# IQ.net
KiCad netlist of a schematic drawn in Altium Designer
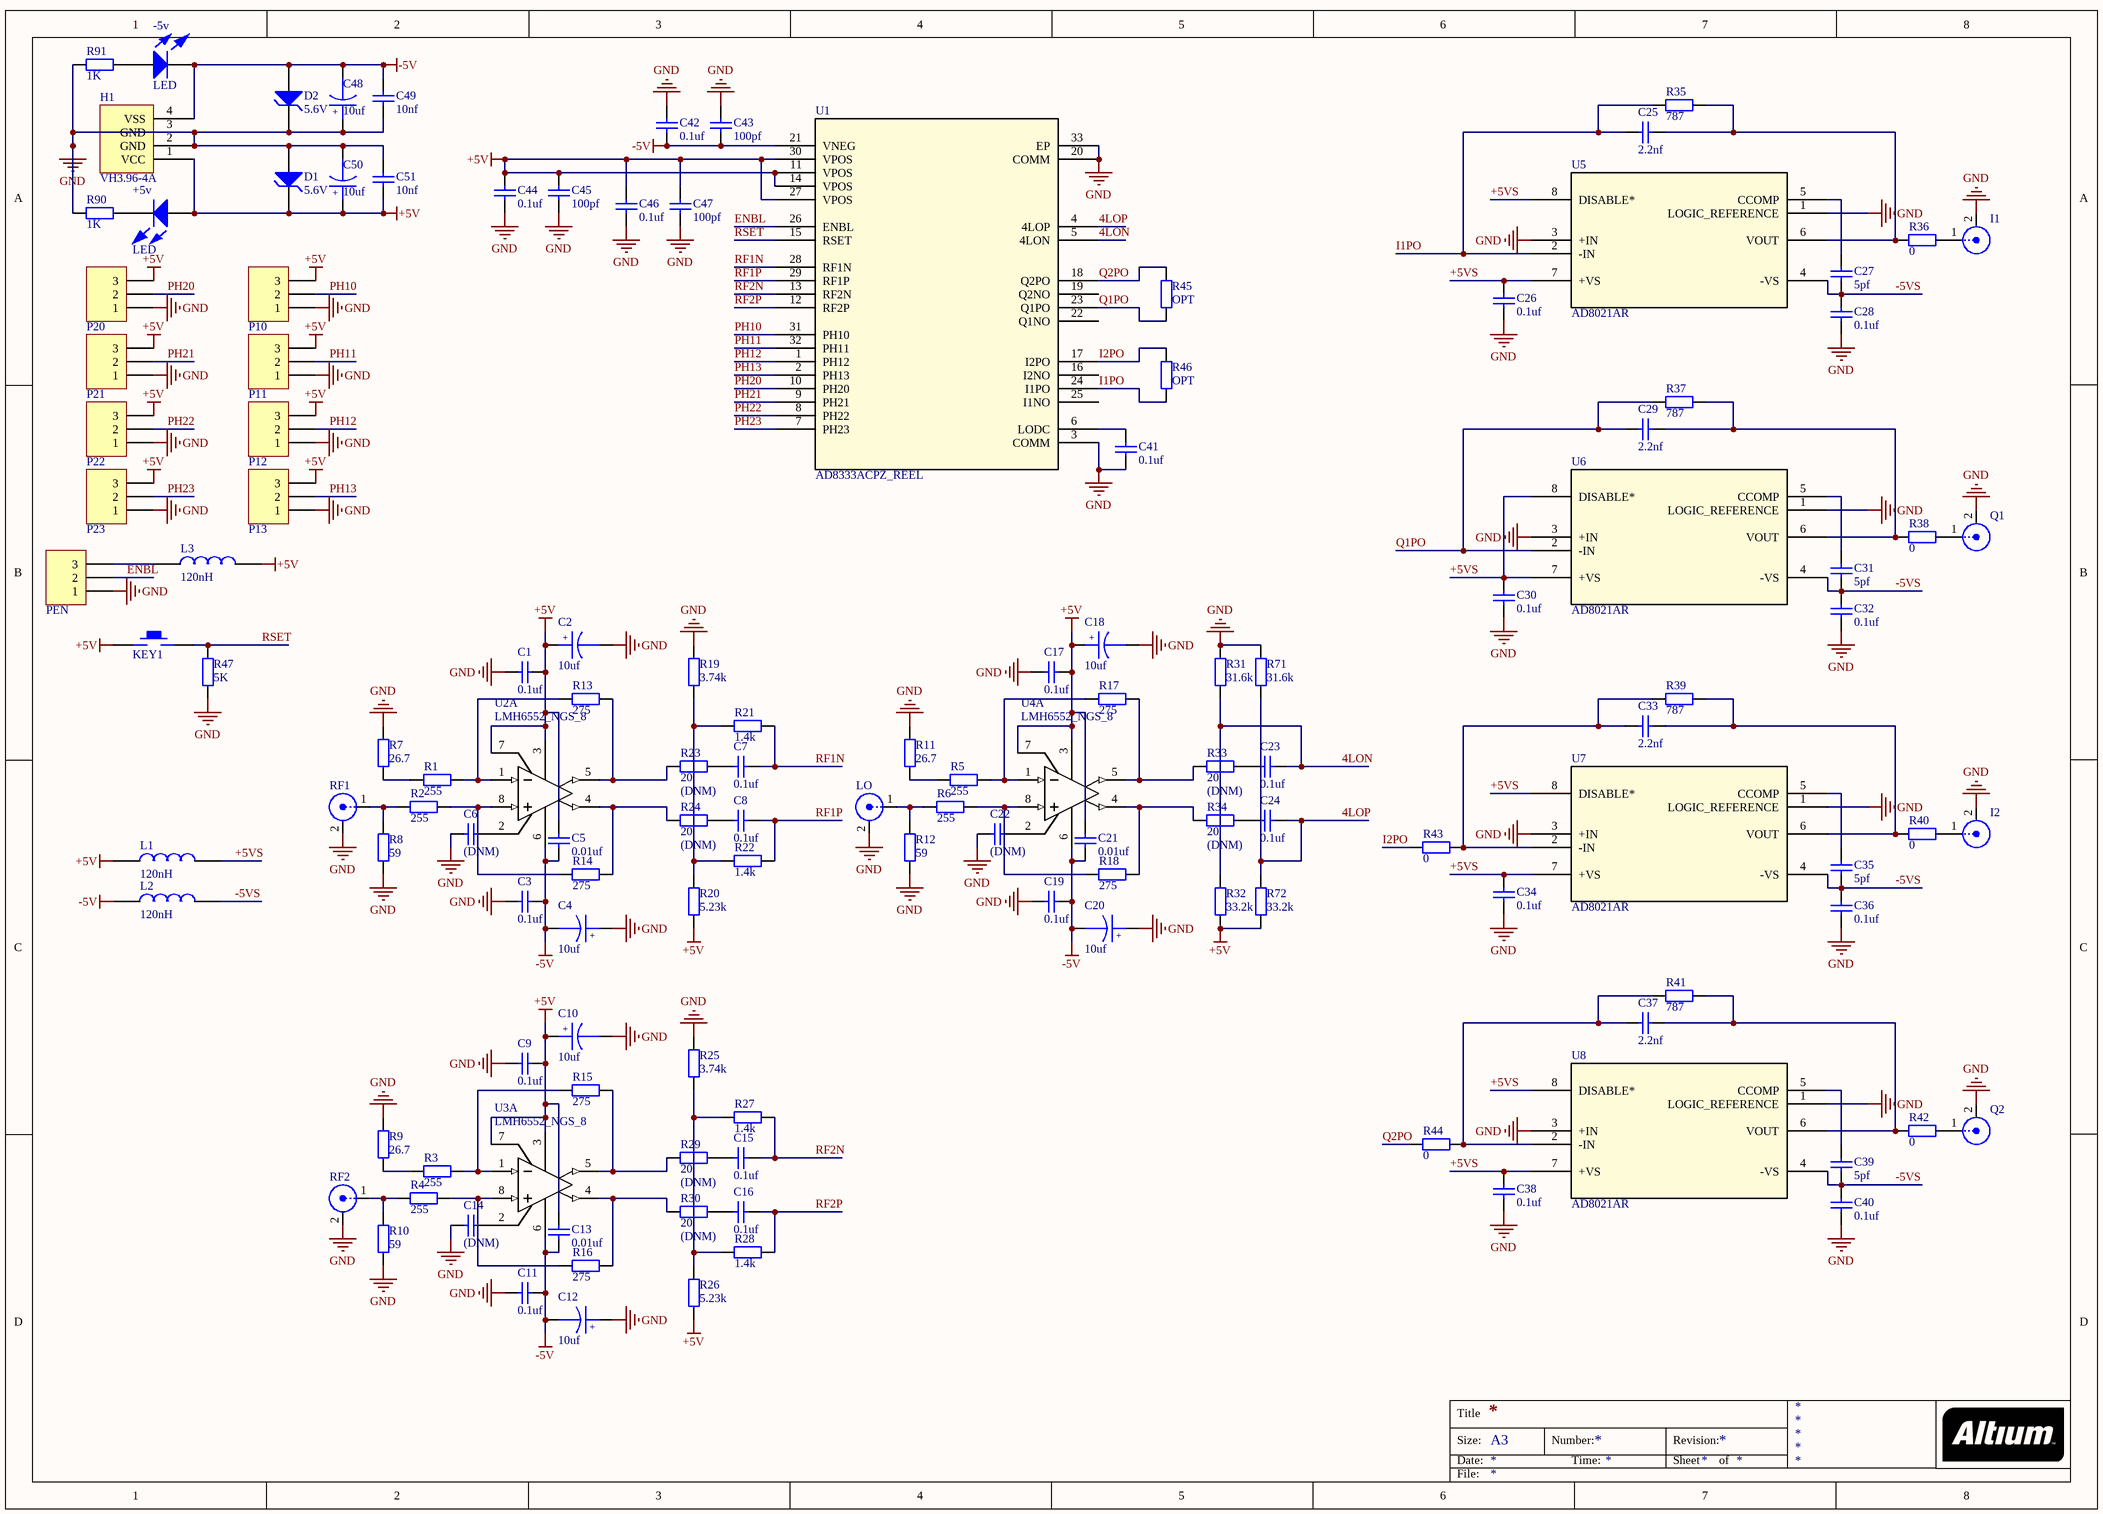
[diagram p0: IQ解调器原理图.SchDoc]

(export (version "E")
  (design (tool "Eeschema 10.0.6"))
  (components
    (comp (ref "+5v") (value "LED") (footprint "0805") (libsource (lib "IQ解调器-原理图") (part "LED")))
    (comp (ref "-5v") (value "LED") (footprint "0805") (libsource (lib "IQ解调器-原理图") (part "LED")))
    (comp (ref "C1")
      (value "0.1uf")
      (footprint "0603C")
      (description "无极性电容")
      (fields (field (name "Comment") "Cap"))
      (libsource (lib "IQ解调器-原理图") (part "Cap"))
    )
    (comp (ref "C2")
      (value "10uf")
      (footprint "3216C-TYPE_A")
      (libsource (lib "IQ解调器-原理图") (part "钽电容Type-A"))
    )
    (comp (ref "C3")
      (value "0.1uf")
      (footprint "0603C")
      (description "无极性电容")
      (fields (field (name "Comment") "Cap"))
      (libsource (lib "IQ解调器-原理图") (part "Cap"))
    )
    (comp (ref "C4")
      (value "10uf")
      (footprint "3216C-TYPE_A")
      (libsource (lib "IQ解调器-原理图") (part "钽电容Type-A"))
    )
    (comp (ref "C5")
      (value "0.01uf")
      (footprint "0603C")
      (description "无极性电容")
      (fields (field (name "Comment") "Cap"))
      (libsource (lib "IQ解调器-原理图") (part "Cap"))
    )
    (comp (ref "C6")
      (value "(DNM)")
      (footprint "0603C")
      (description "无极性电容")
      (fields (field (name "Comment") "Cap"))
      (libsource (lib "IQ解调器-原理图") (part "Cap"))
    )
    (comp (ref "C7")
      (value "0.1uf")
      (footprint "0603C")
      (description "无极性电容")
      (fields (field (name "Comment") "Cap"))
      (libsource (lib "IQ解调器-原理图") (part "Cap"))
    )
    (comp (ref "C8")
      (value "0.1uf")
      (footprint "0603C")
      (description "无极性电容")
      (fields (field (name "Comment") "Cap"))
      (libsource (lib "IQ解调器-原理图") (part "Cap"))
    )
    (comp (ref "C9")
      (value "0.1uf")
      (footprint "0603C")
      (description "无极性电容")
      (fields (field (name "Comment") "Cap"))
      (libsource (lib "IQ解调器-原理图") (part "Cap"))
    )
    (comp (ref "C10")
      (value "10uf")
      (footprint "3216C-TYPE_A")
      (libsource (lib "IQ解调器-原理图") (part "钽电容Type-A"))
    )
    (comp (ref "C11")
      (value "0.1uf")
      (footprint "0603C")
      (description "无极性电容")
      (fields (field (name "Comment") "Cap"))
      (libsource (lib "IQ解调器-原理图") (part "Cap"))
    )
    (comp (ref "C12")
      (value "10uf")
      (footprint "3216C-TYPE_A")
      (libsource (lib "IQ解调器-原理图") (part "钽电容Type-A"))
    )
    (comp (ref "C13")
      (value "0.01uf")
      (footprint "0603C")
      (description "无极性电容")
      (fields (field (name "Comment") "Cap"))
      (libsource (lib "IQ解调器-原理图") (part "Cap"))
    )
    (comp (ref "C14")
      (value "(DNM)")
      (footprint "0603C")
      (description "无极性电容")
      (fields (field (name "Comment") "Cap"))
      (libsource (lib "IQ解调器-原理图") (part "Cap"))
    )
    (comp (ref "C15")
      (value "0.1uf")
      (footprint "0603C")
      (description "无极性电容")
      (fields (field (name "Comment") "Cap"))
      (libsource (lib "IQ解调器-原理图") (part "Cap"))
    )
    (comp (ref "C16")
      (value "0.1uf")
      (footprint "0603C")
      (description "无极性电容")
      (fields (field (name "Comment") "Cap"))
      (libsource (lib "IQ解调器-原理图") (part "Cap"))
    )
    (comp (ref "C17")
      (value "0.1uf")
      (footprint "0603C")
      (description "无极性电容")
      (fields (field (name "Comment") "Cap"))
      (libsource (lib "IQ解调器-原理图") (part "Cap"))
    )
    (comp (ref "C18")
      (value "10uf")
      (footprint "3216C-TYPE_A")
      (libsource (lib "IQ解调器-原理图") (part "钽电容Type-A"))
    )
    (comp (ref "C19")
      (value "0.1uf")
      (footprint "0603C")
      (description "无极性电容")
      (fields (field (name "Comment") "Cap"))
      (libsource (lib "IQ解调器-原理图") (part "Cap"))
    )
    (comp (ref "C20")
      (value "10uf")
      (footprint "3216C-TYPE_A")
      (libsource (lib "IQ解调器-原理图") (part "钽电容Type-A"))
    )
    (comp (ref "C21")
      (value "0.01uf")
      (footprint "0603C")
      (description "无极性电容")
      (fields (field (name "Comment") "Cap"))
      (libsource (lib "IQ解调器-原理图") (part "Cap"))
    )
    (comp (ref "C22")
      (value "(DNM)")
      (footprint "0603C")
      (description "无极性电容")
      (fields (field (name "Comment") "Cap"))
      (libsource (lib "IQ解调器-原理图") (part "Cap"))
    )
    (comp (ref "C23")
      (value "0.1uf")
      (footprint "0603C")
      (description "无极性电容")
      (fields (field (name "Comment") "Cap"))
      (libsource (lib "IQ解调器-原理图") (part "Cap"))
    )
    (comp (ref "C24")
      (value "0.1uf")
      (footprint "0603C")
      (description "无极性电容")
      (fields (field (name "Comment") "Cap"))
      (libsource (lib "IQ解调器-原理图") (part "Cap"))
    )
    (comp (ref "C25")
      (value "2.2nf")
      (footprint "0603C")
      (description "无极性电容")
      (fields (field (name "Comment") "Cap"))
      (libsource (lib "IQ解调器-原理图") (part "Cap"))
    )
    (comp (ref "C26")
      (value "0.1uf")
      (footprint "0603C")
      (description "无极性电容")
      (fields (field (name "Comment") "Cap"))
      (libsource (lib "IQ解调器-原理图") (part "Cap"))
    )
    (comp (ref "C27")
      (value "5pf")
      (footprint "0603C")
      (description "无极性电容")
      (fields (field (name "Comment") "Cap"))
      (libsource (lib "IQ解调器-原理图") (part "Cap"))
    )
    (comp (ref "C28")
      (value "0.1uf")
      (footprint "0603C")
      (description "无极性电容")
      (fields (field (name "Comment") "Cap"))
      (libsource (lib "IQ解调器-原理图") (part "Cap"))
    )
    (comp (ref "C29")
      (value "2.2nf")
      (footprint "0603C")
      (description "无极性电容")
      (fields (field (name "Comment") "Cap"))
      (libsource (lib "IQ解调器-原理图") (part "Cap"))
    )
    (comp (ref "C30")
      (value "0.1uf")
      (footprint "0603C")
      (description "无极性电容")
      (fields (field (name "Comment") "Cap"))
      (libsource (lib "IQ解调器-原理图") (part "Cap"))
    )
    (comp (ref "C31")
      (value "5pf")
      (footprint "0603C")
      (description "无极性电容")
      (fields (field (name "Comment") "Cap"))
      (libsource (lib "IQ解调器-原理图") (part "Cap"))
    )
    (comp (ref "C32")
      (value "0.1uf")
      (footprint "0603C")
      (description "无极性电容")
      (fields (field (name "Comment") "Cap"))
      (libsource (lib "IQ解调器-原理图") (part "Cap"))
    )
    (comp (ref "C33")
      (value "2.2nf")
      (footprint "0603C")
      (description "无极性电容")
      (fields (field (name "Comment") "Cap"))
      (libsource (lib "IQ解调器-原理图") (part "Cap"))
    )
    (comp (ref "C34")
      (value "0.1uf")
      (footprint "0603C")
      (description "无极性电容")
      (fields (field (name "Comment") "Cap"))
      (libsource (lib "IQ解调器-原理图") (part "Cap"))
    )
    (comp (ref "C35")
      (value "5pf")
      (footprint "0603C")
      (description "无极性电容")
      (fields (field (name "Comment") "Cap"))
      (libsource (lib "IQ解调器-原理图") (part "Cap"))
    )
    (comp (ref "C36")
      (value "0.1uf")
      (footprint "0603C")
      (description "无极性电容")
      (fields (field (name "Comment") "Cap"))
      (libsource (lib "IQ解调器-原理图") (part "Cap"))
    )
    (comp (ref "C37")
      (value "2.2nf")
      (footprint "0603C")
      (description "无极性电容")
      (fields (field (name "Comment") "Cap"))
      (libsource (lib "IQ解调器-原理图") (part "Cap"))
    )
    (comp (ref "C38")
      (value "0.1uf")
      (footprint "0603C")
      (description "无极性电容")
      (fields (field (name "Comment") "Cap"))
      (libsource (lib "IQ解调器-原理图") (part "Cap"))
    )
    (comp (ref "C39")
      (value "5pf")
      (footprint "0603C")
      (description "无极性电容")
      (fields (field (name "Comment") "Cap"))
      (libsource (lib "IQ解调器-原理图") (part "Cap"))
    )
    (comp (ref "C40")
      (value "0.1uf")
      (footprint "0603C")
      (description "无极性电容")
      (fields (field (name "Comment") "Cap"))
      (libsource (lib "IQ解调器-原理图") (part "Cap"))
    )
    (comp (ref "C41")
      (value "0.1uf")
      (footprint "0603C")
      (description "无极性电容")
      (fields (field (name "Comment") "Cap"))
      (libsource (lib "IQ解调器-原理图") (part "Cap"))
    )
    (comp (ref "C42")
      (value "0.1uf")
      (footprint "0603C")
      (description "无极性电容")
      (fields (field (name "Comment") "Cap"))
      (libsource (lib "IQ解调器-原理图") (part "Cap"))
    )
    (comp (ref "C43")
      (value "100pf")
      (footprint "0603C")
      (description "无极性电容")
      (fields (field (name "Comment") "Cap"))
      (libsource (lib "IQ解调器-原理图") (part "Cap"))
    )
    (comp (ref "C44")
      (value "0.1uf")
      (footprint "0603C")
      (description "无极性电容")
      (fields (field (name "Comment") "Cap"))
      (libsource (lib "IQ解调器-原理图") (part "Cap"))
    )
    (comp (ref "C45")
      (value "100pf")
      (footprint "0603C")
      (description "无极性电容")
      (fields (field (name "Comment") "Cap"))
      (libsource (lib "IQ解调器-原理图") (part "Cap"))
    )
    (comp (ref "C46")
      (value "0.1uf")
      (footprint "0603C")
      (description "无极性电容")
      (fields (field (name "Comment") "Cap"))
      (libsource (lib "IQ解调器-原理图") (part "Cap"))
    )
    (comp (ref "C47")
      (value "100pf")
      (footprint "0603C")
      (description "无极性电容")
      (fields (field (name "Comment") "Cap"))
      (libsource (lib "IQ解调器-原理图") (part "Cap"))
    )
    (comp (ref "C48")
      (value "10uf")
      (footprint "3216C-TYPE_A")
      (libsource (lib "IQ解调器-原理图") (part "钽电容Type-A"))
    )
    (comp (ref "C49")
      (value "10nf")
      (footprint "0603C")
      (description "无极性电容")
      (fields (field (name "Comment") "Cap"))
      (libsource (lib "IQ解调器-原理图") (part "Cap"))
    )
    (comp (ref "C50")
      (value "10uf")
      (footprint "3216C-TYPE_A")
      (libsource (lib "IQ解调器-原理图") (part "钽电容Type-A"))
    )
    (comp (ref "C51")
      (value "10nf")
      (footprint "0603C")
      (description "无极性电容")
      (fields (field (name "Comment") "Cap"))
      (libsource (lib "IQ解调器-原理图") (part "Cap"))
    )
    (comp (ref "D1")
      (value "5.6V")
      (footprint "SMA/DO-214AC")
      (libsource (lib "IQ解调器-原理图") (part "肖特基-5.6V"))
    )
    (comp (ref "D2")
      (value "5.6V")
      (footprint "SMA/DO-214AC")
      (libsource (lib "IQ解调器-原理图") (part "肖特基-5.6V"))
    )
    (comp (ref "H1")
      (value "VH3.96-4A")
      (footprint "VH3.96-4P")
      (libsource (lib "IQ解调器-原理图") (part "VH3.96-4A"))
    )
    (comp (ref "I1") (value "SMA") (footprint "SMA-2") (libsource (lib "IQ解调器-原理图") (part "SMA-2")))
    (comp (ref "I2") (value "SMA") (footprint "SMA-2") (libsource (lib "IQ解调器-原理图") (part "SMA-2")))
    (comp (ref "KEY1")
      (value "KEY_M")
      (footprint "KEY_M")
      (libsource (lib "MiniSTM32 V3.0封装库") (part "KEY_M"))
    )
    (comp (ref "L1")
      (value "120nH")
      (footprint "0603R")
      (description "0603电感")
      (libsource (lib "IQ解调器-原理图") (part "0603电感"))
    )
    (comp (ref "L2")
      (value "120nH")
      (footprint "0603R")
      (description "0603电感")
      (libsource (lib "IQ解调器-原理图") (part "0603电感"))
    )
    (comp (ref "L3")
      (value "120nH")
      (footprint "0603R")
      (description "0603电感")
      (libsource (lib "IQ解调器-原理图") (part "0603电感"))
    )
    (comp (ref "LO") (value "SMA") (footprint "SMA-2") (libsource (lib "IQ解调器-原理图") (part "SMA-2")))
    (comp (ref "P10")
      (value "Header 3")
      (footprint "HDR3X1_A")
      (description "接插件")
      (libsource (lib "Fszhang") (part "Header 3"))
    )
    (comp (ref "P11")
      (value "Header 3")
      (footprint "HDR3X1_A")
      (description "接插件")
      (libsource (lib "Fszhang") (part "Header 3"))
    )
    (comp (ref "P12")
      (value "Header 3")
      (footprint "HDR3X1_A")
      (description "接插件")
      (libsource (lib "Fszhang") (part "Header 3"))
    )
    (comp (ref "P13")
      (value "Header 3")
      (footprint "HDR3X1_A")
      (description "接插件")
      (libsource (lib "Fszhang") (part "Header 3"))
    )
    (comp (ref "P20")
      (value "Header 3")
      (footprint "HDR3X1_A")
      (description "接插件")
      (libsource (lib "Fszhang") (part "Header 3"))
    )
    (comp (ref "P21")
      (value "Header 3")
      (footprint "HDR3X1_A")
      (description "接插件")
      (libsource (lib "Fszhang") (part "Header 3"))
    )
    (comp (ref "P22")
      (value "Header 3")
      (footprint "HDR3X1_A")
      (description "接插件")
      (libsource (lib "Fszhang") (part "Header 3"))
    )
    (comp (ref "P23")
      (value "Header 3")
      (footprint "HDR3X1_A")
      (description "接插件")
      (libsource (lib "Fszhang") (part "Header 3"))
    )
    (comp (ref "PEN")
      (value "Header 3")
      (footprint "HDR3X1_A")
      (description "接插件")
      (libsource (lib "Fszhang") (part "Header 3"))
    )
    (comp (ref "Q1") (value "SMA") (footprint "SMA-2") (libsource (lib "IQ解调器-原理图") (part "SMA-2")))
    (comp (ref "Q2") (value "SMA") (footprint "SMA-2") (libsource (lib "IQ解调器-原理图") (part "SMA-2")))
    (comp (ref "R1")
      (value "255")
      (footprint "0603R")
      (description "贴片电阻")
      (fields (field (name "Comment") "Res1"))
      (libsource (lib "IQ解调器-原理图") (part "Res1"))
    )
    (comp (ref "R2")
      (value "255")
      (footprint "0603R")
      (description "贴片电阻")
      (fields (field (name "Comment") "Res1"))
      (libsource (lib "IQ解调器-原理图") (part "Res1"))
    )
    (comp (ref "R3")
      (value "255")
      (footprint "0603R")
      (description "贴片电阻")
      (fields (field (name "Comment") "Res1"))
      (libsource (lib "IQ解调器-原理图") (part "Res1"))
    )
    (comp (ref "R4")
      (value "255")
      (footprint "0603R")
      (description "贴片电阻")
      (fields (field (name "Comment") "Res1"))
      (libsource (lib "IQ解调器-原理图") (part "Res1"))
    )
    (comp (ref "R5")
      (value "255")
      (footprint "0603R")
      (description "贴片电阻")
      (fields (field (name "Comment") "Res1"))
      (libsource (lib "IQ解调器-原理图") (part "Res1"))
    )
    (comp (ref "R6")
      (value "255")
      (footprint "0603R")
      (description "贴片电阻")
      (fields (field (name "Comment") "Res1"))
      (libsource (lib "IQ解调器-原理图") (part "Res1"))
    )
    (comp (ref "R7")
      (value "26.7")
      (footprint "0603R")
      (description "贴片电阻")
      (fields (field (name "Comment") "Res1"))
      (libsource (lib "") (part "Res1_1"))
    )
    (comp (ref "R8")
      (value "59")
      (footprint "0603R")
      (description "贴片电阻")
      (fields (field (name "Comment") "Res1"))
      (libsource (lib "") (part "Res1_1"))
    )
    (comp (ref "R9")
      (value "26.7")
      (footprint "0603R")
      (description "贴片电阻")
      (fields (field (name "Comment") "Res1"))
      (libsource (lib "") (part "Res1_1"))
    )
    (comp (ref "R10")
      (value "59")
      (footprint "0603R")
      (description "贴片电阻")
      (fields (field (name "Comment") "Res1"))
      (libsource (lib "") (part "Res1_1"))
    )
    (comp (ref "R11")
      (value "26.7")
      (footprint "0603R")
      (description "贴片电阻")
      (fields (field (name "Comment") "Res1"))
      (libsource (lib "") (part "Res1_1"))
    )
    (comp (ref "R12")
      (value "59")
      (footprint "0603R")
      (description "贴片电阻")
      (fields (field (name "Comment") "Res1"))
      (libsource (lib "") (part "Res1_1"))
    )
    (comp (ref "R13")
      (value "275")
      (footprint "0603R")
      (description "贴片电阻")
      (fields (field (name "Comment") "Res1"))
      (libsource (lib "IQ解调器-原理图") (part "Res1"))
    )
    (comp (ref "R14")
      (value "275")
      (footprint "0603R")
      (description "贴片电阻")
      (fields (field (name "Comment") "Res1"))
      (libsource (lib "IQ解调器-原理图") (part "Res1"))
    )
    (comp (ref "R15")
      (value "275")
      (footprint "0603R")
      (description "贴片电阻")
      (fields (field (name "Comment") "Res1"))
      (libsource (lib "IQ解调器-原理图") (part "Res1"))
    )
    (comp (ref "R16")
      (value "275")
      (footprint "0603R")
      (description "贴片电阻")
      (fields (field (name "Comment") "Res1"))
      (libsource (lib "IQ解调器-原理图") (part "Res1"))
    )
    (comp (ref "R17")
      (value "275")
      (footprint "0603R")
      (description "贴片电阻")
      (fields (field (name "Comment") "Res1"))
      (libsource (lib "IQ解调器-原理图") (part "Res1"))
    )
    (comp (ref "R18")
      (value "275")
      (footprint "0603R")
      (description "贴片电阻")
      (fields (field (name "Comment") "Res1"))
      (libsource (lib "IQ解调器-原理图") (part "Res1"))
    )
    (comp (ref "R19")
      (value "3.74k")
      (footprint "0603R")
      (description "贴片电阻")
      (fields (field (name "Comment") "Res1"))
      (libsource (lib "") (part "Res1_1"))
    )
    (comp (ref "R20")
      (value "5.23k")
      (footprint "0603R")
      (description "贴片电阻")
      (fields (field (name "Comment") "Res1"))
      (libsource (lib "") (part "Res1_1"))
    )
    (comp (ref "R21")
      (value "1.4k")
      (footprint "0603R")
      (description "贴片电阻")
      (fields (field (name "Comment") "Res1"))
      (libsource (lib "") (part "Res1_2"))
    )
    (comp (ref "R22")
      (value "1.4k")
      (footprint "0603R")
      (description "贴片电阻")
      (fields (field (name "Comment") "Res1"))
      (libsource (lib "IQ解调器-原理图") (part "Res1"))
    )
    (comp (ref "R23")
      (value "(DNM)")
      (footprint "0603R")
      (description "贴片电阻")
      (fields (field (name "ALTIUM_VALUE") "20"))
      (libsource (lib "IQ解调器-原理图") (part "Res1"))
    )
    (comp (ref "R24")
      (value "(DNM)")
      (footprint "0603R")
      (description "贴片电阻")
      (fields (field (name "ALTIUM_VALUE") "20"))
      (libsource (lib "IQ解调器-原理图") (part "Res1"))
    )
    (comp (ref "R25")
      (value "3.74k")
      (footprint "0603R")
      (description "贴片电阻")
      (fields (field (name "Comment") "Res1"))
      (libsource (lib "") (part "Res1_1"))
    )
    (comp (ref "R26")
      (value "5.23k")
      (footprint "0603R")
      (description "贴片电阻")
      (fields (field (name "Comment") "Res1"))
      (libsource (lib "") (part "Res1_1"))
    )
    (comp (ref "R27")
      (value "1.4k")
      (footprint "0603R")
      (description "贴片电阻")
      (fields (field (name "Comment") "Res1"))
      (libsource (lib "") (part "Res1_2"))
    )
    (comp (ref "R28")
      (value "1.4k")
      (footprint "0603R")
      (description "贴片电阻")
      (fields (field (name "Comment") "Res1"))
      (libsource (lib "IQ解调器-原理图") (part "Res1"))
    )
    (comp (ref "R29")
      (value "(DNM)")
      (footprint "0603R")
      (description "贴片电阻")
      (fields (field (name "ALTIUM_VALUE") "20"))
      (libsource (lib "IQ解调器-原理图") (part "Res1"))
    )
    (comp (ref "R30")
      (value "(DNM)")
      (footprint "0603R")
      (description "贴片电阻")
      (fields (field (name "ALTIUM_VALUE") "20"))
      (libsource (lib "IQ解调器-原理图") (part "Res1"))
    )
    (comp (ref "R31")
      (value "31.6k")
      (footprint "0603R")
      (description "贴片电阻")
      (fields (field (name "Comment") "Res1"))
      (libsource (lib "") (part "Res1_1"))
    )
    (comp (ref "R32")
      (value "33.2k")
      (footprint "0603R")
      (description "贴片电阻")
      (fields (field (name "Comment") "Res1"))
      (libsource (lib "") (part "Res1_1"))
    )
    (comp (ref "R33")
      (value "(DNM)")
      (footprint "0603R")
      (description "贴片电阻")
      (fields (field (name "ALTIUM_VALUE") "20"))
      (libsource (lib "IQ解调器-原理图") (part "Res1"))
    )
    (comp (ref "R34")
      (value "(DNM)")
      (footprint "0603R")
      (description "贴片电阻")
      (fields (field (name "ALTIUM_VALUE") "20"))
      (libsource (lib "IQ解调器-原理图") (part "Res1"))
    )
    (comp (ref "R35")
      (value "787")
      (footprint "0603R")
      (description "贴片电阻")
      (fields (field (name "Comment") "Res1"))
      (libsource (lib "IQ解调器-原理图") (part "Res1"))
    )
    (comp (ref "R36")
      (value "0")
      (footprint "0603R")
      (description "贴片电阻")
      (fields (field (name "Comment") "Res1"))
      (libsource (lib "IQ解调器-原理图") (part "Res1"))
    )
    (comp (ref "R37")
      (value "787")
      (footprint "0603R")
      (description "贴片电阻")
      (fields (field (name "Comment") "Res1"))
      (libsource (lib "IQ解调器-原理图") (part "Res1"))
    )
    (comp (ref "R38")
      (value "0")
      (footprint "0603R")
      (description "贴片电阻")
      (fields (field (name "Comment") "Res1"))
      (libsource (lib "IQ解调器-原理图") (part "Res1"))
    )
    (comp (ref "R39")
      (value "787")
      (footprint "0603R")
      (description "贴片电阻")
      (fields (field (name "Comment") "Res1"))
      (libsource (lib "IQ解调器-原理图") (part "Res1"))
    )
    (comp (ref "R40")
      (value "0")
      (footprint "0603R")
      (description "贴片电阻")
      (fields (field (name "Comment") "Res1"))
      (libsource (lib "IQ解调器-原理图") (part "Res1"))
    )
    (comp (ref "R41")
      (value "787")
      (footprint "0603R")
      (description "贴片电阻")
      (fields (field (name "Comment") "Res1"))
      (libsource (lib "IQ解调器-原理图") (part "Res1"))
    )
    (comp (ref "R42")
      (value "0")
      (footprint "0603R")
      (description "贴片电阻")
      (fields (field (name "Comment") "Res1"))
      (libsource (lib "IQ解调器-原理图") (part "Res1"))
    )
    (comp (ref "R43")
      (value "0")
      (footprint "0603R")
      (description "贴片电阻")
      (fields (field (name "Comment") "Res1"))
      (libsource (lib "IQ解调器-原理图") (part "Res1"))
    )
    (comp (ref "R44")
      (value "0")
      (footprint "0603R")
      (description "贴片电阻")
      (fields (field (name "Comment") "Res1"))
      (libsource (lib "IQ解调器-原理图") (part "Res1"))
    )
    (comp (ref "R45")
      (value "OPT")
      (footprint "0603R")
      (description "贴片电阻")
      (fields (field (name "Comment") "Res1"))
      (libsource (lib "") (part "Res1_1"))
    )
    (comp (ref "R46")
      (value "OPT")
      (footprint "0603R")
      (description "贴片电阻")
      (fields (field (name "Comment") "Res1"))
      (libsource (lib "") (part "Res1_1"))
    )
    (comp (ref "R47")
      (value "5K")
      (footprint "0603R")
      (description "贴片电阻")
      (fields (field (name "Comment") "Res1"))
      (libsource (lib "") (part "Res1_1"))
    )
    (comp (ref "R71")
      (value "31.6k")
      (footprint "0603R")
      (description "贴片电阻")
      (fields (field (name "Comment") "Res1"))
      (libsource (lib "") (part "Res1_1"))
    )
    (comp (ref "R72")
      (value "33.2k")
      (footprint "0603R")
      (description "贴片电阻")
      (fields (field (name "Comment") "Res1"))
      (libsource (lib "") (part "Res1_1"))
    )
    (comp (ref "R90")
      (value "1K")
      (footprint "0603R")
      (description "贴片电阻")
      (fields (field (name "Comment") "Res1"))
      (libsource (lib "IQ解调器-原理图") (part "Res1"))
    )
    (comp (ref "R91")
      (value "1K")
      (footprint "0603R")
      (description "贴片电阻")
      (fields (field (name "Comment") "Res1"))
      (libsource (lib "IQ解调器-原理图") (part "Res1"))
    )
    (comp (ref "RF1") (value "SMA") (footprint "SMA-2") (libsource (lib "IQ解调器-原理图") (part "SMA-2")))
    (comp (ref "RF2") (value "SMA") (footprint "SMA-2") (libsource (lib "IQ解调器-原理图") (part "SMA-2")))
    (comp (ref "U1")
      (value "AD8333ACPZ_REEL")
      (footprint "CP_32_2")
      (description "Imported")
      (libsource (lib "IQ解调器-原理图") (part "AD8333ACPZ_REEL"))
    )
    (comp (ref "U2")
      (value "LMH6552_NGS_8")
      (footprint "LC-SOIC-8_150mil")
      (description "Imported")
      (fields (field (name "PARTNUMBER") "LMH6552SD") (field (name "MANUFACTURER") "NationalSemiconductor"))
      (libsource (lib "IQ解调器-原理图") (part "LMH6552_NGS_8"))
    )
    (comp (ref "U3")
      (value "LMH6552_NGS_8")
      (footprint "LC-SOIC-8_150mil")
      (description "Imported")
      (fields (field (name "PARTNUMBER") "LMH6552SD") (field (name "MANUFACTURER") "NationalSemiconductor"))
      (libsource (lib "IQ解调器-原理图") (part "LMH6552_NGS_8"))
    )
    (comp (ref "U4")
      (value "LMH6552_NGS_8")
      (footprint "LC-SOIC-8_150mil")
      (description "Imported")
      (fields (field (name "PARTNUMBER") "LMH6552SD") (field (name "MANUFACTURER") "NationalSemiconductor"))
      (libsource (lib "IQ解调器-原理图") (part "LMH6552_NGS_8"))
    )
    (comp (ref "U5")
      (value "AD8021AR")
      (footprint "R_8")
      (description "Imported")
      (libsource (lib "IQ解调器-原理图") (part "AD8021AR"))
    )
    (comp (ref "U6")
      (value "AD8021AR")
      (footprint "R_8")
      (description "Imported")
      (libsource (lib "IQ解调器-原理图") (part "AD8021AR"))
    )
    (comp (ref "U7")
      (value "AD8021AR")
      (footprint "R_8")
      (description "Imported")
      (libsource (lib "IQ解调器-原理图") (part "AD8021AR"))
    )
    (comp (ref "U8")
      (value "AD8021AR")
      (footprint "R_8")
      (description "Imported")
      (libsource (lib "IQ解调器-原理图") (part "AD8021AR"))
    )
  )
  (nets
    (net (code "1") (name "+5V") (class "Default")
      (node (ref "+5v") (pin "1") (pinfunction "A_1") (pintype "passive"))
      (node (ref "C1") (pin "2") (pinfunction "2_2") (pintype "passive"))
      (node (ref "C10") (pin "1") (pinfunction "1_1") (pintype "passive"))
      (node (ref "C13") (pin "2") (pinfunction "2_2") (pintype "passive"))
      (node (ref "C17") (pin "2") (pinfunction "2_2") (pintype "passive"))
      (node (ref "C18") (pin "1") (pinfunction "1_1") (pintype "passive"))
      (node (ref "C2") (pin "1") (pinfunction "1_1") (pintype "passive"))
      (node (ref "C21") (pin "2") (pinfunction "2_2") (pintype "passive"))
      (node (ref "C44") (pin "2") (pinfunction "2_2") (pintype "passive"))
      (node (ref "C45") (pin "2") (pinfunction "2_2") (pintype "passive"))
      (node (ref "C46") (pin "2") (pinfunction "2_2") (pintype "passive"))
      (node (ref "C47") (pin "2") (pinfunction "2_2") (pintype "passive"))
      (node (ref "C5") (pin "2") (pinfunction "2_2") (pintype "passive"))
      (node (ref "C50") (pin "1") (pinfunction "1_1") (pintype "passive"))
      (node (ref "C51") (pin "1") (pinfunction "1_1") (pintype "passive"))
      (node (ref "C9") (pin "2") (pinfunction "2_2") (pintype "passive"))
      (node (ref "D1") (pin "2") (pinfunction "K_2") (pintype "passive"))
      (node (ref "H1") (pin "1") (pinfunction "VCC_1") (pintype "passive"))
      (node (ref "KEY1") (pin "1") (pinfunction "1_1") (pintype "passive"))
      (node (ref "L1") (pin "1") (pintype "passive"))
      (node (ref "L3") (pin "2") (pintype "passive"))
      (node (ref "P10") (pin "3") (pinfunction "3_3") (pintype "passive"))
      (node (ref "P11") (pin "3") (pinfunction "3_3") (pintype "passive"))
      (node (ref "P12") (pin "3") (pinfunction "3_3") (pintype "passive"))
      (node (ref "P13") (pin "3") (pinfunction "3_3") (pintype "passive"))
      (node (ref "P20") (pin "3") (pinfunction "3_3") (pintype "passive"))
      (node (ref "P21") (pin "3") (pinfunction "3_3") (pintype "passive"))
      (node (ref "P22") (pin "3") (pinfunction "3_3") (pintype "passive"))
      (node (ref "P23") (pin "3") (pinfunction "3_3") (pintype "passive"))
      (node (ref "R20") (pin "1") (pinfunction "1_1") (pintype "passive"))
      (node (ref "R26") (pin "1") (pinfunction "1_1") (pintype "passive"))
      (node (ref "R32") (pin "1") (pinfunction "1_1") (pintype "passive"))
      (node (ref "R72") (pin "1") (pinfunction "1_1") (pintype "passive"))
      (node (ref "U1") (pin "11") (pinfunction "VPOS_11") (pintype "passive"))
      (node (ref "U1") (pin "14") (pinfunction "VPOS_14") (pintype "passive"))
      (node (ref "U1") (pin "27") (pinfunction "VPOS_27") (pintype "passive"))
      (node (ref "U1") (pin "30") (pinfunction "VPOS_30") (pintype "passive"))
      (node (ref "U2") (pin "3") (pinfunction "V+_3") (pintype "power_in"))
      (node (ref "U2") (pin "7") (pinfunction "EN_7") (pintype "passive"))
      (node (ref "U3") (pin "3") (pinfunction "V+_3") (pintype "power_in"))
      (node (ref "U3") (pin "7") (pinfunction "EN_7") (pintype "passive"))
      (node (ref "U4") (pin "3") (pinfunction "V+_3") (pintype "power_in"))
      (node (ref "U4") (pin "7") (pinfunction "EN_7") (pintype "passive"))
    )
    (net (code "2") (name "-5V") (class "Default")
      (node (ref "-5v") (pin "2") (pinfunction "K_2") (pintype "passive"))
      (node (ref "C11") (pin "1") (pinfunction "1_1") (pintype "passive"))
      (node (ref "C12") (pin "2") (pinfunction "2_2") (pintype "passive"))
      (node (ref "C13") (pin "1") (pinfunction "1_1") (pintype "passive"))
      (node (ref "C19") (pin "1") (pinfunction "1_1") (pintype "passive"))
      (node (ref "C20") (pin "2") (pinfunction "2_2") (pintype "passive"))
      (node (ref "C21") (pin "1") (pinfunction "1_1") (pintype "passive"))
      (node (ref "C3") (pin "1") (pinfunction "1_1") (pintype "passive"))
      (node (ref "C4") (pin "2") (pinfunction "2_2") (pintype "passive"))
      (node (ref "C42") (pin "1") (pinfunction "1_1") (pintype "passive"))
      (node (ref "C43") (pin "1") (pinfunction "1_1") (pintype "passive"))
      (node (ref "C48") (pin "2") (pinfunction "2_2") (pintype "passive"))
      (node (ref "C49") (pin "2") (pinfunction "2_2") (pintype "passive"))
      (node (ref "C5") (pin "1") (pinfunction "1_1") (pintype "passive"))
      (node (ref "D2") (pin "1") (pinfunction "A_1") (pintype "passive"))
      (node (ref "H1") (pin "4") (pinfunction "VSS_4") (pintype "passive"))
      (node (ref "L2") (pin "1") (pintype "passive"))
      (node (ref "U1") (pin "21") (pinfunction "VNEG_21") (pintype "passive"))
      (node (ref "U2") (pin "6") (pinfunction "V-_6") (pintype "power_in"))
      (node (ref "U3") (pin "6") (pinfunction "V-_6") (pintype "power_in"))
      (node (ref "U4") (pin "6") (pinfunction "V-_6") (pintype "power_in"))
    )
    (net (code "3") (name "/+5VS") (class "Default")
      (node (ref "C26") (pin "2") (pinfunction "2_2") (pintype "passive"))
      (node (ref "C30") (pin "2") (pinfunction "2_2") (pintype "passive"))
      (node (ref "C34") (pin "2") (pinfunction "2_2") (pintype "passive"))
      (node (ref "C38") (pin "2") (pinfunction "2_2") (pintype "passive"))
      (node (ref "L1") (pin "2") (pintype "passive"))
      (node (ref "U5") (pin "7") (pinfunction "+VS_7") (pintype "power_in"))
      (node (ref "U5") (pin "8") (pinfunction "DISABLE*_8") (pintype "passive"))
      (node (ref "U6") (pin "7") (pinfunction "+VS_7") (pintype "power_in"))
      (node (ref "U6") (pin "8") (pinfunction "DISABLE*_8") (pintype "passive"))
      (node (ref "U7") (pin "7") (pinfunction "+VS_7") (pintype "power_in"))
      (node (ref "U7") (pin "8") (pinfunction "DISABLE*_8") (pintype "passive"))
      (node (ref "U8") (pin "7") (pinfunction "+VS_7") (pintype "power_in"))
      (node (ref "U8") (pin "8") (pinfunction "DISABLE*_8") (pintype "passive"))
    )
    (net (code "4") (name "/-5VS") (class "Default")
      (node (ref "C27") (pin "2") (pinfunction "2_2") (pintype "passive"))
      (node (ref "C28") (pin "2") (pinfunction "2_2") (pintype "passive"))
      (node (ref "C31") (pin "2") (pinfunction "2_2") (pintype "passive"))
      (node (ref "C32") (pin "2") (pinfunction "2_2") (pintype "passive"))
      (node (ref "C35") (pin "2") (pinfunction "2_2") (pintype "passive"))
      (node (ref "C36") (pin "2") (pinfunction "2_2") (pintype "passive"))
      (node (ref "C39") (pin "2") (pinfunction "2_2") (pintype "passive"))
      (node (ref "C40") (pin "2") (pinfunction "2_2") (pintype "passive"))
      (node (ref "L2") (pin "2") (pintype "passive"))
      (node (ref "U5") (pin "4") (pinfunction "-VS_4") (pintype "power_in"))
      (node (ref "U6") (pin "4") (pinfunction "-VS_4") (pintype "power_in"))
      (node (ref "U7") (pin "4") (pinfunction "-VS_4") (pintype "power_in"))
      (node (ref "U8") (pin "4") (pinfunction "-VS_4") (pintype "power_in"))
    )
    (net (code "5") (name "/4LON") (class "Default")
      (node (ref "C23") (pin "2") (pinfunction "2_2") (pintype "passive"))
      (node (ref "R31") (pin "1") (pinfunction "1_1") (pintype "passive"))
      (node (ref "R32") (pin "2") (pinfunction "2_2") (pintype "passive"))
      (node (ref "U1") (pin "5") (pinfunction "4LON_5") (pintype "passive"))
    )
    (net (code "6") (name "/4LOP") (class "Default")
      (node (ref "C24") (pin "2") (pinfunction "2_2") (pintype "passive"))
      (node (ref "R71") (pin "1") (pinfunction "1_1") (pintype "passive"))
      (node (ref "R72") (pin "2") (pinfunction "2_2") (pintype "passive"))
      (node (ref "U1") (pin "4") (pinfunction "4LOP_4") (pintype "passive"))
    )
    (net (code "7") (name "/ENBL") (class "Default")
      (node (ref "PEN") (pin "2") (pinfunction "2_2") (pintype "passive"))
      (node (ref "U1") (pin "26") (pinfunction "ENBL_26") (pintype "power_in"))
    )
    (net (code "8") (name "/I1PO") (class "Default")
      (node (ref "C25") (pin "1") (pinfunction "1_1") (pintype "passive"))
      (node (ref "R35") (pin "1") (pinfunction "1_1") (pintype "passive"))
      (node (ref "R46") (pin "1") (pinfunction "1_1") (pintype "passive"))
      (node (ref "U1") (pin "24") (pinfunction "I1PO_24") (pintype "passive"))
      (node (ref "U5") (pin "2") (pinfunction "-IN_2") (pintype "passive"))
    )
    (net (code "9") (name "/I2PO") (class "Default")
      (node (ref "R43") (pin "1") (pinfunction "1_1") (pintype "passive"))
      (node (ref "R46") (pin "2") (pinfunction "2_2") (pintype "passive"))
      (node (ref "U1") (pin "17") (pinfunction "I2PO_17") (pintype "passive"))
    )
    (net (code "10") (name "/PH10") (class "Default")
      (node (ref "P10") (pin "2") (pinfunction "2_2") (pintype "passive"))
      (node (ref "U1") (pin "31") (pinfunction "PH10_31") (pintype "passive"))
    )
    (net (code "11") (name "/PH11") (class "Default")
      (node (ref "P11") (pin "2") (pinfunction "2_2") (pintype "passive"))
      (node (ref "U1") (pin "32") (pinfunction "PH11_32") (pintype "passive"))
    )
    (net (code "12") (name "/PH12") (class "Default")
      (node (ref "P12") (pin "2") (pinfunction "2_2") (pintype "passive"))
      (node (ref "U1") (pin "1") (pinfunction "PH12_1") (pintype "passive"))
    )
    (net (code "13") (name "/PH13") (class "Default")
      (node (ref "P13") (pin "2") (pinfunction "2_2") (pintype "passive"))
      (node (ref "U1") (pin "2") (pinfunction "PH13_2") (pintype "passive"))
    )
    (net (code "14") (name "/PH20") (class "Default")
      (node (ref "P20") (pin "2") (pinfunction "2_2") (pintype "passive"))
      (node (ref "U1") (pin "10") (pinfunction "PH20_10") (pintype "passive"))
    )
    (net (code "15") (name "/PH21") (class "Default")
      (node (ref "P21") (pin "2") (pinfunction "2_2") (pintype "passive"))
      (node (ref "U1") (pin "9") (pinfunction "PH21_9") (pintype "passive"))
    )
    (net (code "16") (name "/PH22") (class "Default")
      (node (ref "P22") (pin "2") (pinfunction "2_2") (pintype "passive"))
      (node (ref "U1") (pin "8") (pinfunction "PH22_8") (pintype "passive"))
    )
    (net (code "17") (name "/PH23") (class "Default")
      (node (ref "P23") (pin "2") (pinfunction "2_2") (pintype "passive"))
      (node (ref "U1") (pin "7") (pinfunction "PH23_7") (pintype "passive"))
    )
    (net (code "18") (name "/Q1PO") (class "Default")
      (node (ref "C29") (pin "1") (pinfunction "1_1") (pintype "passive"))
      (node (ref "R37") (pin "1") (pinfunction "1_1") (pintype "passive"))
      (node (ref "R45") (pin "1") (pinfunction "1_1") (pintype "passive"))
      (node (ref "U1") (pin "23") (pinfunction "Q1PO_23") (pintype "passive"))
      (node (ref "U6") (pin "2") (pinfunction "-IN_2") (pintype "passive"))
    )
    (net (code "19") (name "/Q2PO") (class "Default")
      (node (ref "R44") (pin "1") (pinfunction "1_1") (pintype "passive"))
      (node (ref "R45") (pin "2") (pinfunction "2_2") (pintype "passive"))
      (node (ref "U1") (pin "18") (pinfunction "Q2PO_18") (pintype "passive"))
    )
    (net (code "20") (name "/RF1N") (class "Default")
      (node (ref "C7") (pin "2") (pinfunction "2_2") (pintype "passive"))
      (node (ref "R21") (pin "1") (pinfunction "1_1") (pintype "passive"))
      (node (ref "U1") (pin "28") (pinfunction "RF1N_28") (pintype "passive"))
    )
    (net (code "21") (name "/RF1P") (class "Default")
      (node (ref "C8") (pin "2") (pinfunction "2_2") (pintype "passive"))
      (node (ref "R22") (pin "2") (pinfunction "2_2") (pintype "passive"))
      (node (ref "U1") (pin "29") (pinfunction "RF1P_29") (pintype "passive"))
    )
    (net (code "22") (name "/RF2N") (class "Default")
      (node (ref "C15") (pin "2") (pinfunction "2_2") (pintype "passive"))
      (node (ref "R27") (pin "1") (pinfunction "1_1") (pintype "passive"))
      (node (ref "U1") (pin "13") (pinfunction "RF2N_13") (pintype "passive"))
    )
    (net (code "23") (name "/RF2P") (class "Default")
      (node (ref "C16") (pin "2") (pinfunction "2_2") (pintype "passive"))
      (node (ref "R28") (pin "2") (pinfunction "2_2") (pintype "passive"))
      (node (ref "U1") (pin "12") (pinfunction "RF2P_12") (pintype "passive"))
    )
    (net (code "24") (name "/RSET") (class "Default")
      (node (ref "KEY1") (pin "2") (pinfunction "2_2") (pintype "passive"))
      (node (ref "R47") (pin "2") (pinfunction "2_2") (pintype "passive"))
      (node (ref "U1") (pin "15") (pinfunction "RSET_15") (pintype "power_in"))
    )
    (net (code "25") (name "GND") (class "Default")
      (node (ref "C1") (pin "1") (pinfunction "1_1") (pintype "passive"))
      (node (ref "C10") (pin "2") (pinfunction "2_2") (pintype "passive"))
      (node (ref "C11") (pin "2") (pinfunction "2_2") (pintype "passive"))
      (node (ref "C12") (pin "1") (pinfunction "1_1") (pintype "passive"))
      (node (ref "C14") (pin "1") (pinfunction "1_1") (pintype "passive"))
      (node (ref "C17") (pin "1") (pinfunction "1_1") (pintype "passive"))
      (node (ref "C18") (pin "2") (pinfunction "2_2") (pintype "passive"))
      (node (ref "C19") (pin "2") (pinfunction "2_2") (pintype "passive"))
      (node (ref "C2") (pin "2") (pinfunction "2_2") (pintype "passive"))
      (node (ref "C20") (pin "1") (pinfunction "1_1") (pintype "passive"))
      (node (ref "C22") (pin "1") (pinfunction "1_1") (pintype "passive"))
      (node (ref "C26") (pin "1") (pinfunction "1_1") (pintype "passive"))
      (node (ref "C28") (pin "1") (pinfunction "1_1") (pintype "passive"))
      (node (ref "C3") (pin "2") (pinfunction "2_2") (pintype "passive"))
      (node (ref "C30") (pin "1") (pinfunction "1_1") (pintype "passive"))
      (node (ref "C32") (pin "1") (pinfunction "1_1") (pintype "passive"))
      (node (ref "C34") (pin "1") (pinfunction "1_1") (pintype "passive"))
      (node (ref "C36") (pin "1") (pinfunction "1_1") (pintype "passive"))
      (node (ref "C38") (pin "1") (pinfunction "1_1") (pintype "passive"))
      (node (ref "C4") (pin "1") (pinfunction "1_1") (pintype "passive"))
      (node (ref "C40") (pin "1") (pinfunction "1_1") (pintype "passive"))
      (node (ref "C41") (pin "1") (pinfunction "1_1") (pintype "passive"))
      (node (ref "C42") (pin "2") (pinfunction "2_2") (pintype "passive"))
      (node (ref "C43") (pin "2") (pinfunction "2_2") (pintype "passive"))
      (node (ref "C44") (pin "1") (pinfunction "1_1") (pintype "passive"))
      (node (ref "C45") (pin "1") (pinfunction "1_1") (pintype "passive"))
      (node (ref "C46") (pin "1") (pinfunction "1_1") (pintype "passive"))
      (node (ref "C47") (pin "1") (pinfunction "1_1") (pintype "passive"))
      (node (ref "C48") (pin "1") (pinfunction "1_1") (pintype "passive"))
      (node (ref "C49") (pin "1") (pinfunction "1_1") (pintype "passive"))
      (node (ref "C50") (pin "2") (pinfunction "2_2") (pintype "passive"))
      (node (ref "C51") (pin "2") (pinfunction "2_2") (pintype "passive"))
      (node (ref "C6") (pin "1") (pinfunction "1_1") (pintype "passive"))
      (node (ref "C9") (pin "1") (pinfunction "1_1") (pintype "passive"))
      (node (ref "D1") (pin "1") (pinfunction "A_1") (pintype "passive"))
      (node (ref "D2") (pin "2") (pinfunction "K_2") (pintype "passive"))
      (node (ref "H1") (pin "2") (pinfunction "GND_2") (pintype "passive"))
      (node (ref "H1") (pin "3") (pinfunction "GND_3") (pintype "passive"))
      (node (ref "I1") (pin "2") (pinfunction "GND_2") (pintype "passive"))
      (node (ref "I2") (pin "2") (pinfunction "GND_2") (pintype "passive"))
      (node (ref "LO") (pin "2") (pinfunction "GND_2") (pintype "passive"))
      (node (ref "P10") (pin "1") (pinfunction "1_1") (pintype "passive"))
      (node (ref "P11") (pin "1") (pinfunction "1_1") (pintype "passive"))
      (node (ref "P12") (pin "1") (pinfunction "1_1") (pintype "passive"))
      (node (ref "P13") (pin "1") (pinfunction "1_1") (pintype "passive"))
      (node (ref "P20") (pin "1") (pinfunction "1_1") (pintype "passive"))
      (node (ref "P21") (pin "1") (pinfunction "1_1") (pintype "passive"))
      (node (ref "P22") (pin "1") (pinfunction "1_1") (pintype "passive"))
      (node (ref "P23") (pin "1") (pinfunction "1_1") (pintype "passive"))
      (node (ref "PEN") (pin "1") (pinfunction "1_1") (pintype "passive"))
      (node (ref "Q1") (pin "2") (pinfunction "GND_2") (pintype "passive"))
      (node (ref "Q2") (pin "2") (pinfunction "GND_2") (pintype "passive"))
      (node (ref "R10") (pin "1") (pinfunction "1_1") (pintype "passive"))
      (node (ref "R11") (pin "2") (pinfunction "2_2") (pintype "passive"))
      (node (ref "R12") (pin "1") (pinfunction "1_1") (pintype "passive"))
      (node (ref "R19") (pin "2") (pinfunction "2_2") (pintype "passive"))
      (node (ref "R25") (pin "2") (pinfunction "2_2") (pintype "passive"))
      (node (ref "R31") (pin "2") (pinfunction "2_2") (pintype "passive"))
      (node (ref "R47") (pin "1") (pinfunction "1_1") (pintype "passive"))
      (node (ref "R7") (pin "2") (pinfunction "2_2") (pintype "passive"))
      (node (ref "R71") (pin "2") (pinfunction "2_2") (pintype "passive"))
      (node (ref "R8") (pin "1") (pinfunction "1_1") (pintype "passive"))
      (node (ref "R9") (pin "2") (pinfunction "2_2") (pintype "passive"))
      (node (ref "R90") (pin "1") (pinfunction "1_1") (pintype "passive"))
      (node (ref "R91") (pin "1") (pinfunction "1_1") (pintype "passive"))
      (node (ref "RF1") (pin "2") (pinfunction "GND_2") (pintype "passive"))
      (node (ref "RF2") (pin "2") (pinfunction "GND_2") (pintype "passive"))
      (node (ref "U1") (pin "20") (pinfunction "COMM_20") (pintype "passive"))
      (node (ref "U1") (pin "3") (pinfunction "COMM_3") (pintype "power_in"))
      (node (ref "U1") (pin "33") (pinfunction "EP_33") (pintype "passive"))
      (node (ref "U5") (pin "1") (pinfunction "LOGIC_REFERENCE_1") (pintype "passive"))
      (node (ref "U5") (pin "3") (pinfunction "+IN_3") (pintype "passive"))
      (node (ref "U6") (pin "1") (pinfunction "LOGIC_REFERENCE_1") (pintype "passive"))
      (node (ref "U6") (pin "3") (pinfunction "+IN_3") (pintype "passive"))
      (node (ref "U7") (pin "1") (pinfunction "LOGIC_REFERENCE_1") (pintype "passive"))
      (node (ref "U7") (pin "3") (pinfunction "+IN_3") (pintype "passive"))
      (node (ref "U8") (pin "1") (pinfunction "LOGIC_REFERENCE_1") (pintype "passive"))
      (node (ref "U8") (pin "3") (pinfunction "+IN_3") (pintype "passive"))
    )
    (net (code "26") (name "Net-(+5v-K)") (class "Default")
      (node (ref "+5v") (pin "2") (pinfunction "K_2") (pintype "passive"))
      (node (ref "R90") (pin "2") (pinfunction "2_2") (pintype "passive"))
    )
    (net (code "27") (name "Net-(-5v-A)") (class "Default")
      (node (ref "-5v") (pin "1") (pinfunction "A_1") (pintype "passive"))
      (node (ref "R91") (pin "2") (pinfunction "2_2") (pintype "passive"))
    )
    (net (code "28") (name "Net-(C7-Pad1)") (class "Default")
      (node (ref "C7") (pin "1") (pinfunction "1_1") (pintype "passive"))
      (node (ref "R23") (pin "2") (pinfunction "2_2") (pintype "passive"))
    )
    (net (code "29") (name "Net-(C8-Pad1)") (class "Default")
      (node (ref "C8") (pin "1") (pinfunction "1_1") (pintype "passive"))
      (node (ref "R24") (pin "2") (pinfunction "2_2") (pintype "passive"))
    )
    (net (code "30") (name "Net-(C15-Pad1)") (class "Default")
      (node (ref "C15") (pin "1") (pinfunction "1_1") (pintype "passive"))
      (node (ref "R29") (pin "2") (pinfunction "2_2") (pintype "passive"))
    )
    (net (code "31") (name "Net-(C16-Pad1)") (class "Default")
      (node (ref "C16") (pin "1") (pinfunction "1_1") (pintype "passive"))
      (node (ref "R30") (pin "2") (pinfunction "2_2") (pintype "passive"))
    )
    (net (code "32") (name "Net-(C23-Pad1)") (class "Default")
      (node (ref "C23") (pin "1") (pinfunction "1_1") (pintype "passive"))
      (node (ref "R33") (pin "2") (pinfunction "2_2") (pintype "passive"))
    )
    (net (code "33") (name "Net-(C24-Pad1)") (class "Default")
      (node (ref "C24") (pin "1") (pinfunction "1_1") (pintype "passive"))
      (node (ref "R34") (pin "2") (pinfunction "2_2") (pintype "passive"))
    )
    (net (code "34") (name "Net-(I1-Signal)") (class "Default")
      (node (ref "I1") (pin "1") (pinfunction "Signal_1") (pintype "passive"))
      (node (ref "R36") (pin "2") (pinfunction "2_2") (pintype "passive"))
    )
    (net (code "35") (name "Net-(I2-Signal)") (class "Default")
      (node (ref "I2") (pin "1") (pinfunction "Signal_1") (pintype "passive"))
      (node (ref "R40") (pin "2") (pinfunction "2_2") (pintype "passive"))
    )
    (net (code "36") (name "Net-(L3-Pad1)") (class "Default")
      (node (ref "L3") (pin "1") (pintype "passive"))
      (node (ref "PEN") (pin "3") (pinfunction "3_3") (pintype "passive"))
    )
    (net (code "37") (name "Net-(LO-Signal)") (class "Default")
      (node (ref "LO") (pin "1") (pinfunction "Signal_1") (pintype "passive"))
      (node (ref "R12") (pin "2") (pinfunction "2_2") (pintype "passive"))
      (node (ref "R6") (pin "1") (pinfunction "1_1") (pintype "passive"))
    )
    (net (code "38") (name "Net-(Q1-Signal)") (class "Default")
      (node (ref "Q1") (pin "1") (pinfunction "Signal_1") (pintype "passive"))
      (node (ref "R38") (pin "2") (pinfunction "2_2") (pintype "passive"))
    )
    (net (code "39") (name "Net-(Q2-Signal)") (class "Default")
      (node (ref "Q2") (pin "1") (pinfunction "Signal_1") (pintype "passive"))
      (node (ref "R42") (pin "2") (pinfunction "2_2") (pintype "passive"))
    )
    (net (code "40") (name "Net-(R1-Pad1)") (class "Default")
      (node (ref "R1") (pin "1") (pinfunction "1_1") (pintype "passive"))
      (node (ref "R7") (pin "1") (pinfunction "1_1") (pintype "passive"))
    )
    (net (code "41") (name "Net-(R3-Pad1)") (class "Default")
      (node (ref "R3") (pin "1") (pinfunction "1_1") (pintype "passive"))
      (node (ref "R9") (pin "1") (pinfunction "1_1") (pintype "passive"))
    )
    (net (code "42") (name "Net-(R11-Pad1)") (class "Default")
      (node (ref "R11") (pin "1") (pinfunction "1_1") (pintype "passive"))
      (node (ref "R5") (pin "1") (pinfunction "1_1") (pintype "passive"))
    )
    (net (code "43") (name "Net-(R19-Pad1)") (class "Default")
      (node (ref "R19") (pin "1") (pinfunction "1_1") (pintype "passive"))
      (node (ref "R20") (pin "2") (pinfunction "2_2") (pintype "passive"))
      (node (ref "R21") (pin "2") (pinfunction "2_2") (pintype "passive"))
      (node (ref "R22") (pin "1") (pinfunction "1_1") (pintype "passive"))
    )
    (net (code "44") (name "Net-(R25-Pad1)") (class "Default")
      (node (ref "R25") (pin "1") (pinfunction "1_1") (pintype "passive"))
      (node (ref "R26") (pin "2") (pinfunction "2_2") (pintype "passive"))
      (node (ref "R27") (pin "2") (pinfunction "2_2") (pintype "passive"))
      (node (ref "R28") (pin "1") (pinfunction "1_1") (pintype "passive"))
    )
    (net (code "45") (name "Net-(RF1-Signal)") (class "Default")
      (node (ref "R2") (pin "1") (pinfunction "1_1") (pintype "passive"))
      (node (ref "R8") (pin "2") (pinfunction "2_2") (pintype "passive"))
      (node (ref "RF1") (pin "1") (pinfunction "Signal_1") (pintype "passive"))
    )
    (net (code "46") (name "Net-(RF2-Signal)") (class "Default")
      (node (ref "R10") (pin "2") (pinfunction "2_2") (pintype "passive"))
      (node (ref "R4") (pin "1") (pinfunction "1_1") (pintype "passive"))
      (node (ref "RF2") (pin "1") (pinfunction "Signal_1") (pintype "passive"))
    )
    (net (code "47") (name "Net-(U1-LODC)") (class "Default")
      (node (ref "C41") (pin "2") (pinfunction "2_2") (pintype "passive"))
      (node (ref "U1") (pin "6") (pinfunction "LODC_6") (pintype "passive"))
    )
    (net (code "48") (name "Net-(U2A-IN+)") (class "Default")
      (node (ref "R14") (pin "1") (pinfunction "1_1") (pintype "passive"))
      (node (ref "R2") (pin "2") (pinfunction "2_2") (pintype "passive"))
      (node (ref "U2") (pin "8") (pinfunction "IN+_8") (pintype "input"))
    )
    (net (code "49") (name "Net-(U2A-IN-)") (class "Default")
      (node (ref "R1") (pin "2") (pinfunction "2_2") (pintype "passive"))
      (node (ref "R13") (pin "1") (pinfunction "1_1") (pintype "passive"))
      (node (ref "U2") (pin "1") (pinfunction "IN-_1") (pintype "input"))
    )
    (net (code "50") (name "Net-(U2A-OUT+)") (class "Default")
      (node (ref "R14") (pin "2") (pinfunction "2_2") (pintype "passive"))
      (node (ref "R24") (pin "1") (pinfunction "1_1") (pintype "passive"))
      (node (ref "U2") (pin "4") (pinfunction "OUT+_4") (pintype "output"))
    )
    (net (code "51") (name "Net-(U2A-OUT-)") (class "Default")
      (node (ref "R13") (pin "2") (pinfunction "2_2") (pintype "passive"))
      (node (ref "R23") (pin "1") (pinfunction "1_1") (pintype "passive"))
      (node (ref "U2") (pin "5") (pinfunction "OUT-_5") (pintype "output"))
    )
    (net (code "52") (name "Net-(U2A-VCM)") (class "Default")
      (node (ref "C6") (pin "2") (pinfunction "2_2") (pintype "passive"))
      (node (ref "U2") (pin "2") (pinfunction "VCM_2") (pintype "passive"))
    )
    (net (code "53") (name "Net-(U3A-IN+)") (class "Default")
      (node (ref "R16") (pin "1") (pinfunction "1_1") (pintype "passive"))
      (node (ref "R4") (pin "2") (pinfunction "2_2") (pintype "passive"))
      (node (ref "U3") (pin "8") (pinfunction "IN+_8") (pintype "input"))
    )
    (net (code "54") (name "Net-(U3A-IN-)") (class "Default")
      (node (ref "R15") (pin "1") (pinfunction "1_1") (pintype "passive"))
      (node (ref "R3") (pin "2") (pinfunction "2_2") (pintype "passive"))
      (node (ref "U3") (pin "1") (pinfunction "IN-_1") (pintype "input"))
    )
    (net (code "55") (name "Net-(U3A-OUT+)") (class "Default")
      (node (ref "R16") (pin "2") (pinfunction "2_2") (pintype "passive"))
      (node (ref "R30") (pin "1") (pinfunction "1_1") (pintype "passive"))
      (node (ref "U3") (pin "4") (pinfunction "OUT+_4") (pintype "output"))
    )
    (net (code "56") (name "Net-(U3A-OUT-)") (class "Default")
      (node (ref "R15") (pin "2") (pinfunction "2_2") (pintype "passive"))
      (node (ref "R29") (pin "1") (pinfunction "1_1") (pintype "passive"))
      (node (ref "U3") (pin "5") (pinfunction "OUT-_5") (pintype "output"))
    )
    (net (code "57") (name "Net-(U3A-VCM)") (class "Default")
      (node (ref "C14") (pin "2") (pinfunction "2_2") (pintype "passive"))
      (node (ref "U3") (pin "2") (pinfunction "VCM_2") (pintype "passive"))
    )
    (net (code "58") (name "Net-(U4A-IN+)") (class "Default")
      (node (ref "R18") (pin "1") (pinfunction "1_1") (pintype "passive"))
      (node (ref "R6") (pin "2") (pinfunction "2_2") (pintype "passive"))
      (node (ref "U4") (pin "8") (pinfunction "IN+_8") (pintype "input"))
    )
    (net (code "59") (name "Net-(U4A-IN-)") (class "Default")
      (node (ref "R17") (pin "1") (pinfunction "1_1") (pintype "passive"))
      (node (ref "R5") (pin "2") (pinfunction "2_2") (pintype "passive"))
      (node (ref "U4") (pin "1") (pinfunction "IN-_1") (pintype "input"))
    )
    (net (code "60") (name "Net-(U4A-OUT+)") (class "Default")
      (node (ref "R18") (pin "2") (pinfunction "2_2") (pintype "passive"))
      (node (ref "R34") (pin "1") (pinfunction "1_1") (pintype "passive"))
      (node (ref "U4") (pin "4") (pinfunction "OUT+_4") (pintype "output"))
    )
    (net (code "61") (name "Net-(U4A-OUT-)") (class "Default")
      (node (ref "R17") (pin "2") (pinfunction "2_2") (pintype "passive"))
      (node (ref "R33") (pin "1") (pinfunction "1_1") (pintype "passive"))
      (node (ref "U4") (pin "5") (pinfunction "OUT-_5") (pintype "output"))
    )
    (net (code "62") (name "Net-(U4A-VCM)") (class "Default")
      (node (ref "C22") (pin "2") (pinfunction "2_2") (pintype "passive"))
      (node (ref "U4") (pin "2") (pinfunction "VCM_2") (pintype "passive"))
    )
    (net (code "63") (name "Net-(U5-CCOMP)") (class "Default")
      (node (ref "C27") (pin "1") (pinfunction "1_1") (pintype "passive"))
      (node (ref "U5") (pin "5") (pinfunction "CCOMP_5") (pintype "passive"))
    )
    (net (code "64") (name "Net-(U5-VOUT)") (class "Default")
      (node (ref "C25") (pin "2") (pinfunction "2_2") (pintype "passive"))
      (node (ref "R35") (pin "2") (pinfunction "2_2") (pintype "passive"))
      (node (ref "R36") (pin "1") (pinfunction "1_1") (pintype "passive"))
      (node (ref "U5") (pin "6") (pinfunction "VOUT_6") (pintype "passive"))
    )
    (net (code "65") (name "Net-(U6-CCOMP)") (class "Default")
      (node (ref "C31") (pin "1") (pinfunction "1_1") (pintype "passive"))
      (node (ref "U6") (pin "5") (pinfunction "CCOMP_5") (pintype "passive"))
    )
    (net (code "66") (name "Net-(U6-VOUT)") (class "Default")
      (node (ref "C29") (pin "2") (pinfunction "2_2") (pintype "passive"))
      (node (ref "R37") (pin "2") (pinfunction "2_2") (pintype "passive"))
      (node (ref "R38") (pin "1") (pinfunction "1_1") (pintype "passive"))
      (node (ref "U6") (pin "6") (pinfunction "VOUT_6") (pintype "passive"))
    )
    (net (code "67") (name "Net-(U7--IN)") (class "Default")
      (node (ref "C33") (pin "1") (pinfunction "1_1") (pintype "passive"))
      (node (ref "R39") (pin "1") (pinfunction "1_1") (pintype "passive"))
      (node (ref "R43") (pin "2") (pinfunction "2_2") (pintype "passive"))
      (node (ref "U7") (pin "2") (pinfunction "-IN_2") (pintype "passive"))
    )
    (net (code "68") (name "Net-(U7-CCOMP)") (class "Default")
      (node (ref "C35") (pin "1") (pinfunction "1_1") (pintype "passive"))
      (node (ref "U7") (pin "5") (pinfunction "CCOMP_5") (pintype "passive"))
    )
    (net (code "69") (name "Net-(U7-VOUT)") (class "Default")
      (node (ref "C33") (pin "2") (pinfunction "2_2") (pintype "passive"))
      (node (ref "R39") (pin "2") (pinfunction "2_2") (pintype "passive"))
      (node (ref "R40") (pin "1") (pinfunction "1_1") (pintype "passive"))
      (node (ref "U7") (pin "6") (pinfunction "VOUT_6") (pintype "passive"))
    )
    (net (code "70") (name "Net-(U8--IN)") (class "Default")
      (node (ref "C37") (pin "1") (pinfunction "1_1") (pintype "passive"))
      (node (ref "R41") (pin "1") (pinfunction "1_1") (pintype "passive"))
      (node (ref "R44") (pin "2") (pinfunction "2_2") (pintype "passive"))
      (node (ref "U8") (pin "2") (pinfunction "-IN_2") (pintype "passive"))
    )
    (net (code "71") (name "Net-(U8-CCOMP)") (class "Default")
      (node (ref "C39") (pin "1") (pinfunction "1_1") (pintype "passive"))
      (node (ref "U8") (pin "5") (pinfunction "CCOMP_5") (pintype "passive"))
    )
    (net (code "72") (name "Net-(U8-VOUT)") (class "Default")
      (node (ref "C37") (pin "2") (pinfunction "2_2") (pintype "passive"))
      (node (ref "R41") (pin "2") (pinfunction "2_2") (pintype "passive"))
      (node (ref "R42") (pin "1") (pinfunction "1_1") (pintype "passive"))
      (node (ref "U8") (pin "6") (pinfunction "VOUT_6") (pintype "passive"))
    )
    (net (code "73") (name "unconnected-(U1-I1NO-Pad25)") (class "Default")
      (node (ref "U1") (pin "25") (pinfunction "I1NO_25") (pintype "passive"))
    )
    (net (code "74") (name "unconnected-(U1-I2NO-Pad16)") (class "Default")
      (node (ref "U1") (pin "16") (pinfunction "I2NO_16") (pintype "passive"))
    )
    (net (code "75") (name "unconnected-(U1-Q1NO-Pad22)") (class "Default")
      (node (ref "U1") (pin "22") (pinfunction "Q1NO_22") (pintype "passive"))
    )
    (net (code "76") (name "unconnected-(U1-Q2NO-Pad19)") (class "Default")
      (node (ref "U1") (pin "19") (pinfunction "Q2NO_19") (pintype "passive"))
    )
  )
)
